# main.net
KiCad netlist of a schematic drawn in Altium Designer
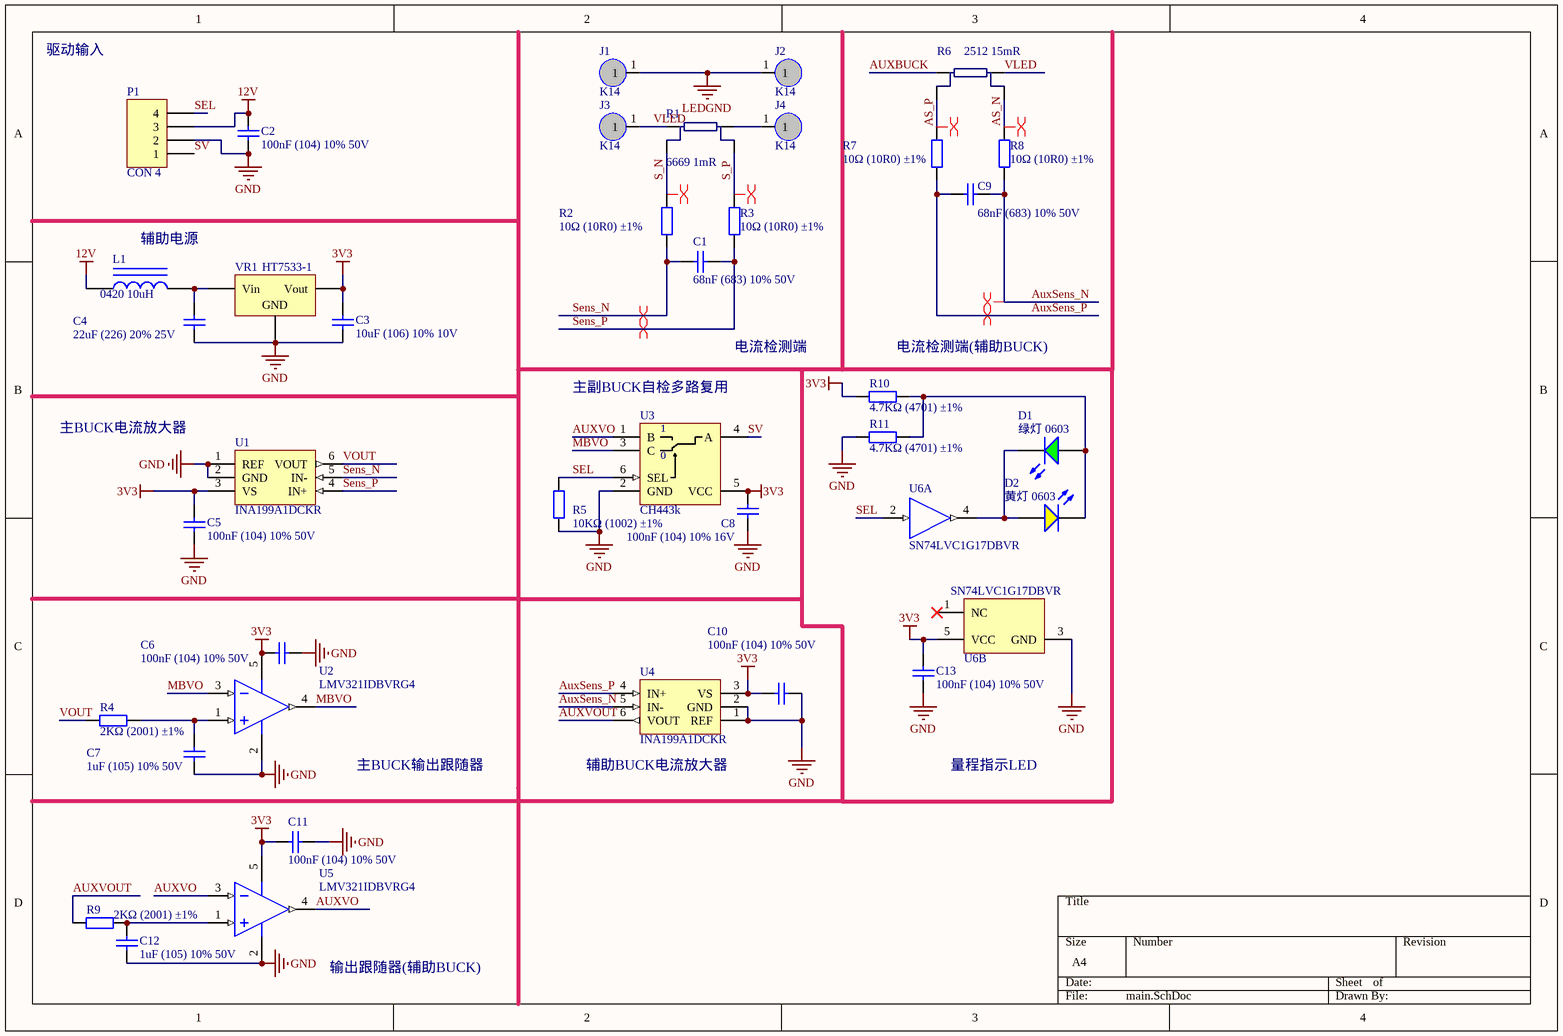
[diagram p0: main.SchDoc]

(export (version "E")
  (design (tool "Eeschema 10.0.6"))
  (components
    (comp (ref "C1")
      (value "68nF (683) 10% 50V")
      (footprint "0603_C")
      (description "贴片电容")
      (libsource (lib "Miscellaneous Devices LC") (part "0603 68nF (683) 10% 50V"))
    )
    (comp (ref "C2")
      (value "100nF (104) 10% 50V")
      (footprint "0603_C")
      (description "贴片电容")
      (libsource (lib "Miscellaneous Devices LC") (part "0603 100nF (104) 10% 50V"))
    )
    (comp (ref "C3")
      (value "10uF (106) 10% 10V")
      (footprint "0603_C")
      (description "贴片电容")
      (libsource (lib "Miscellaneous Devices LC") (part "0603 10uF (106) 10% 10V"))
    )
    (comp (ref "C4")
      (value "22uF (226) 20% 25V")
      (footprint "0805_C")
      (description "贴片电容")
      (libsource (lib "Miscellaneous Devices LC") (part "0805 22uF (226) 20% 25V"))
    )
    (comp (ref "C5")
      (value "100nF (104) 10% 50V")
      (footprint "0603_C")
      (description "贴片电容")
      (libsource (lib "Miscellaneous Devices LC") (part "0603 100nF (104) 10% 50V"))
    )
    (comp (ref "C6")
      (value "100nF (104) 10% 50V")
      (footprint "0603_C")
      (description "贴片电容")
      (libsource (lib "Miscellaneous Devices LC") (part "0603 100nF (104) 10% 50V"))
    )
    (comp (ref "C7")
      (value "1uF (105) 10% 50V")
      (footprint "0603_C")
      (description "贴片电容")
      (libsource (lib "Miscellaneous Devices LC") (part "0603 1uF (105) 10% 50V"))
    )
    (comp (ref "C8")
      (value "100nF (104) 10% 16V")
      (footprint "0402_C")
      (description "贴片电容")
      (libsource (lib "Miscellaneous Devices LC") (part "0402 100nF (104) 10% 16V"))
    )
    (comp (ref "C9")
      (value "68nF (683) 10% 50V")
      (footprint "0603_C")
      (description "贴片电容")
      (libsource (lib "Miscellaneous Devices LC") (part "0603 68nF (683) 10% 50V"))
    )
    (comp (ref "C10")
      (value "100nF (104) 10% 50V")
      (footprint "0603_C")
      (description "贴片电容")
      (libsource (lib "Miscellaneous Devices LC") (part "0603 100nF (104) 10% 50V"))
    )
    (comp (ref "C11")
      (value "100nF (104) 10% 50V")
      (footprint "0603_C")
      (description "贴片电容")
      (libsource (lib "Miscellaneous Devices LC") (part "0603 100nF (104) 10% 50V"))
    )
    (comp (ref "C12")
      (value "1uF (105) 10% 50V")
      (footprint "0603_C")
      (description "贴片电容")
      (libsource (lib "Miscellaneous Devices LC") (part "0603 1uF (105) 10% 50V"))
    )
    (comp (ref "C13")
      (value "100nF (104) 10% 50V")
      (footprint "0603_C")
      (description "贴片电容")
      (libsource (lib "Miscellaneous Devices LC") (part "0603 100nF (104) 10% 50V"))
    )
    (comp (ref "D1")
      (value "绿灯 0603")
      (footprint "0603_LED_S1")
      (description "发光二极管")
      (libsource (lib "Miscellaneous Devices LC") (part "0603 绿灯"))
    )
    (comp (ref "D2")
      (value "黄灯 0603")
      (footprint "0603_LED_S1")
      (description "发光二极管")
      (libsource (lib "Miscellaneous Devices LC") (part "0603 黄灯"))
    )
    (comp (ref "J1") (value "K14") (footprint "k14端子") (libsource (lib "山猫的集成库20190318") (part "Con 1")))
    (comp (ref "J2") (value "K14") (footprint "k14端子") (libsource (lib "山猫的集成库20190318") (part "Con 1")))
    (comp (ref "J3") (value "K14") (footprint "k14端子") (libsource (lib "山猫的集成库20190318") (part "Con 1")))
    (comp (ref "J4") (value "K14") (footprint "k14端子") (libsource (lib "山猫的集成库20190318") (part "Con 1")))
    (comp (ref "L1")
      (value "0420")
      (footprint "IND0420")
      (description "Magnetic-Core Inductor")
      (fields (field (name "ALTIUM_VALUE") "10uH") (field (name "PUBLISHER") "Altium Limited"))
      (libsource (lib "Miscellaneous Devices") (part "Inductor Iron"))
    )
    (comp (ref "P1")
      (value "CON 4")
      (footprint "KF2EDGR5.08/4")
      (description "4-Pin")
      (fields (field (name "PUBLISHER") "Altium Limited"))
      (libsource (lib "山猫的集成库20190318") (part "CON 4"))
    )
    (comp (ref "R1")
      (value "6669 1mR")
      (footprint "Shunt6669")
      (description "4wire shunt 6669 1mR")
      (libsource (lib "custom") (part "shunt"))
    )
    (comp (ref "R2")
      (value "10Ω (10R0) ±1%")
      (footprint "0603_R")
      (description "贴片电阻")
      (libsource (lib "Miscellaneous Devices LC") (part "0603 10Ω (10R0) 1%"))
    )
    (comp (ref "R3")
      (value "10Ω (10R0) ±1%")
      (footprint "0603_R")
      (description "贴片电阻")
      (libsource (lib "Miscellaneous Devices LC") (part "0603 10Ω (10R0) 1%"))
    )
    (comp (ref "R4")
      (value "2KΩ (2001) ±1%")
      (footprint "0603_R")
      (description "贴片电阻")
      (libsource (lib "Miscellaneous Devices LC") (part "0603 2KΩ (2001) 1%"))
    )
    (comp (ref "R5")
      (value "10KΩ (1002) ±1%")
      (footprint "0402_R")
      (description "贴片电阻")
      (libsource (lib "Miscellaneous Devices LC") (part "0402 10KΩ (1002) 1%"))
    )
    (comp (ref "R6")
      (value "2512 15mR")
      (footprint "2512-Virtual4Wire")
      (description "2512检流电阻 15mR")
      (libsource (lib "custom") (part "shunt"))
    )
    (comp (ref "R7")
      (value "10Ω (10R0) ±1%")
      (footprint "0603_R")
      (description "贴片电阻")
      (libsource (lib "Miscellaneous Devices LC") (part "0603 10Ω (10R0) 1%"))
    )
    (comp (ref "R8")
      (value "10Ω (10R0) ±1%")
      (footprint "0603_R")
      (description "贴片电阻")
      (libsource (lib "Miscellaneous Devices LC") (part "0603 10Ω (10R0) 1%"))
    )
    (comp (ref "R9")
      (value "2KΩ (2001) ±1%")
      (footprint "0603_R")
      (description "贴片电阻")
      (libsource (lib "Miscellaneous Devices LC") (part "0603 2KΩ (2001) 1%"))
    )
    (comp (ref "R10")
      (value "4.7KΩ (4701) ±1%")
      (footprint "0603_R")
      (description "贴片电阻")
      (libsource (lib "Miscellaneous Devices LC") (part "0603 4.7KΩ (4701) 1%"))
    )
    (comp (ref "R11")
      (value "4.7KΩ (4701) ±1%")
      (footprint "0603_R")
      (description "贴片电阻")
      (libsource (lib "Miscellaneous Devices LC") (part "0603 4.7KΩ (4701) 1%"))
    )
    (comp (ref "U1")
      (value "INA199A1DCKR")
      (footprint "SC70-6")
      (description "50Khz 50V/V 26V Max High Side Current Op Amp.")
      (libsource (lib "") (part "INA199A2DCKR_1"))
    )
    (comp (ref "U2")
      (value "LMV321IDBVRG4")
      (footprint "SOT-23-5")
      (description "运放")
      (libsource (lib "Miscellaneous Devices LC") (part "LMV321IDBVRG4_[C7972]"))
    )
    (comp (ref "U3")
      (value "CH443k")
      (footprint "SC70-6")
      (description "Low-Voltage Analog Switch SPDT,1.8-5V Power")
      (libsource (lib "custom") (part "NC7SB3157P6X"))
    )
    (comp (ref "U4")
      (value "INA199A1DCKR")
      (footprint "SC70-6")
      (description "50Khz 50V/V 26V Max High Side Current Op Amp.")
      (libsource (lib "custom") (part "INA199A2DCKR"))
    )
    (comp (ref "U5")
      (value "LMV321IDBVRG4")
      (footprint "SOT-23-5")
      (description "运放")
      (libsource (lib "Miscellaneous Devices LC") (part "LMV321IDBVRG4_[C7972]"))
    )
    (comp (ref "U6")
      (value "SN74LVC1G17DBVR")
      (footprint "DBV0005A_N")
      (description "Single Schmitt-Trigger Buffer, DBV0005A, LARGE T&R")
      (fields
        (field (name "GENERIC PART NUMBER") "SN74LVC1G17")
        (field (name "MANUFACTURER") "Texas Instruments")
      )
      (libsource (lib "TI_Logic_Little_Logic") (part "SN74LVC1G17DBVR"))
    )
    (comp (ref "VR1")
      (value "HT7533-1")
      (footprint "SOT-89(SOT-89-3)")
      (description "低压差线性稳压(LDO)")
      (libsource (lib "Miscellaneous Devices LC") (part "SOT-89 HT7533-1"))
    )
  )
  (nets
    (net (code "1") (name "/AS_N") (class "Default")
      (node (ref "R6") (pin "3") (pinfunction "CIN_3") (pintype "passive"))
      (node (ref "R8") (pin "2") (pinfunction "2_2") (pintype "passive"))
    )
    (net (code "2") (name "/AS_P") (class "Default")
      (node (ref "R6") (pin "2") (pinfunction "CIN_2") (pintype "passive"))
      (node (ref "R7") (pin "2") (pinfunction "2_2") (pintype "passive"))
    )
    (net (code "3") (name "/AUXBUCK") (class "Default")
      (node (ref "R6") (pin "0") (pinfunction "CIN_0") (pintype "passive"))
    )
    (net (code "4") (name "/AUXVO") (class "Default")
      (node (ref "U3") (pin "1") (pinfunction "B_1") (pintype "passive"))
      (node (ref "U5") (pin "3") (pinfunction "IN-_3") (pintype "input"))
      (node (ref "U5") (pin "4") (pinfunction "OUT_4") (pintype "output"))
    )
    (net (code "5") (name "/AUXVOUT") (class "Default")
      (node (ref "R9") (pin "1") (pinfunction "1_1") (pintype "passive"))
      (node (ref "U4") (pin "6") (pinfunction "VOUT_6") (pintype "output"))
    )
    (net (code "6") (name "/AuxSens_N") (class "Default")
      (node (ref "C9") (pin "2") (pinfunction "2_2") (pintype "passive"))
      (node (ref "R8") (pin "1") (pinfunction "1_1") (pintype "passive"))
      (node (ref "U4") (pin "5") (pinfunction "IN-_5") (pintype "input"))
    )
    (net (code "7") (name "/AuxSens_P") (class "Default")
      (node (ref "C9") (pin "1") (pinfunction "1_1") (pintype "passive"))
      (node (ref "R7") (pin "1") (pinfunction "1_1") (pintype "passive"))
      (node (ref "U4") (pin "4") (pinfunction "IN+_4") (pintype "input"))
    )
    (net (code "8") (name "/MBVO") (class "Default")
      (node (ref "U2") (pin "3") (pinfunction "IN-_3") (pintype "input"))
      (node (ref "U2") (pin "4") (pinfunction "OUT_4") (pintype "output"))
      (node (ref "U3") (pin "3") (pinfunction "C_3") (pintype "passive"))
    )
    (net (code "9") (name "/SEL") (class "Default")
      (node (ref "P1") (pin "4") (pinfunction "4_4") (pintype "passive"))
      (node (ref "R5") (pin "2") (pinfunction "2_2") (pintype "passive"))
      (node (ref "U3") (pin "6") (pinfunction "SEL_6") (pintype "input"))
      (node (ref "U6") (pin "2") (pinfunction "A_2") (pintype "input"))
    )
    (net (code "10") (name "/SV") (class "Default")
      (node (ref "P1") (pin "1") (pinfunction "1_1") (pintype "passive"))
      (node (ref "U3") (pin "4") (pinfunction "A_4") (pintype "passive"))
    )
    (net (code "11") (name "/S_N") (class "Default")
      (node (ref "R1") (pin "2") (pinfunction "CIN_2") (pintype "passive"))
      (node (ref "R2") (pin "2") (pinfunction "2_2") (pintype "passive"))
    )
    (net (code "12") (name "/S_P") (class "Default")
      (node (ref "R1") (pin "3") (pinfunction "CIN_3") (pintype "passive"))
      (node (ref "R3") (pin "2") (pinfunction "2_2") (pintype "passive"))
    )
    (net (code "13") (name "/Sens_N") (class "Default")
      (node (ref "C1") (pin "1") (pinfunction "1_1") (pintype "passive"))
      (node (ref "R2") (pin "1") (pinfunction "1_1") (pintype "passive"))
      (node (ref "U1") (pin "5") (pinfunction "IN-_5") (pintype "input"))
    )
    (net (code "14") (name "/Sens_P") (class "Default")
      (node (ref "C1") (pin "2") (pinfunction "2_2") (pintype "passive"))
      (node (ref "R3") (pin "1") (pinfunction "1_1") (pintype "passive"))
      (node (ref "U1") (pin "4") (pinfunction "IN+_4") (pintype "input"))
    )
    (net (code "15") (name "/VLED") (class "Default")
      (node (ref "J3") (pin "1") (pinfunction "1_1") (pintype "passive"))
      (node (ref "R1") (pin "0") (pinfunction "CIN_0") (pintype "passive"))
      (node (ref "R6") (pin "1") (pinfunction "CIN_1") (pintype "passive"))
    )
    (net (code "16") (name "/VOUT") (class "Default")
      (node (ref "R4") (pin "1") (pinfunction "1_1") (pintype "passive"))
      (node (ref "U1") (pin "6") (pinfunction "VOUT_6") (pintype "output"))
    )
    (net (code "17") (name "3V3") (class "Default")
      (node (ref "C10") (pin "2") (pinfunction "2_2") (pintype "passive"))
      (node (ref "C11") (pin "1") (pinfunction "1_1") (pintype "passive"))
      (node (ref "C13") (pin "2") (pinfunction "2_2") (pintype "passive"))
      (node (ref "C3") (pin "2") (pinfunction "2_2") (pintype "passive"))
      (node (ref "C5") (pin "2") (pinfunction "2_2") (pintype "passive"))
      (node (ref "C6") (pin "1") (pinfunction "1_1") (pintype "passive"))
      (node (ref "C8") (pin "2") (pinfunction "2_2") (pintype "passive"))
      (node (ref "R10") (pin "2") (pinfunction "2_2") (pintype "passive"))
      (node (ref "U1") (pin "3") (pinfunction "VS_3") (pintype "passive"))
      (node (ref "U2") (pin "5") (pinfunction "V+_5") (pintype "power_in"))
      (node (ref "U3") (pin "5") (pinfunction "VCC_5") (pintype "power_in"))
      (node (ref "U4") (pin "3") (pinfunction "VS_3") (pintype "passive"))
      (node (ref "U5") (pin "5") (pinfunction "V+_5") (pintype "power_in"))
      (node (ref "U6") (pin "5") (pinfunction "VCC_5") (pintype "power_in"))
      (node (ref "VR1") (pin "3") (pinfunction "Vout_3") (pintype "passive"))
    )
    (net (code "18") (name "12V") (class "Default")
      (node (ref "C2") (pin "2") (pinfunction "2_2") (pintype "passive"))
      (node (ref "L1") (pin "1") (pinfunction "1_1") (pintype "passive"))
      (node (ref "P1") (pin "3") (pinfunction "3_3") (pintype "passive"))
    )
    (net (code "19") (name "GND") (class "Default")
      (node (ref "C10") (pin "1") (pinfunction "1_1") (pintype "passive"))
      (node (ref "C11") (pin "2") (pinfunction "2_2") (pintype "passive"))
      (node (ref "C12") (pin "1") (pinfunction "1_1") (pintype "passive"))
      (node (ref "C13") (pin "1") (pinfunction "1_1") (pintype "passive"))
      (node (ref "C2") (pin "1") (pinfunction "1_1") (pintype "passive"))
      (node (ref "C3") (pin "1") (pinfunction "1_1") (pintype "passive"))
      (node (ref "C4") (pin "1") (pinfunction "1_1") (pintype "passive"))
      (node (ref "C5") (pin "1") (pinfunction "1_1") (pintype "passive"))
      (node (ref "C6") (pin "2") (pinfunction "2_2") (pintype "passive"))
      (node (ref "C7") (pin "1") (pinfunction "1_1") (pintype "passive"))
      (node (ref "C8") (pin "1") (pinfunction "1_1") (pintype "passive"))
      (node (ref "P1") (pin "2") (pinfunction "2_2") (pintype "passive"))
      (node (ref "R11") (pin "2") (pinfunction "2_2") (pintype "passive"))
      (node (ref "R5") (pin "1") (pinfunction "1_1") (pintype "passive"))
      (node (ref "U1") (pin "1") (pinfunction "REF_1") (pintype "passive"))
      (node (ref "U1") (pin "2") (pinfunction "GND_2") (pintype "passive"))
      (node (ref "U2") (pin "2") (pinfunction "V-_2") (pintype "power_in"))
      (node (ref "U3") (pin "2") (pinfunction "GND_2") (pintype "power_in"))
      (node (ref "U4") (pin "1") (pinfunction "REF_1") (pintype "passive"))
      (node (ref "U4") (pin "2") (pinfunction "GND_2") (pintype "passive"))
      (node (ref "U5") (pin "2") (pinfunction "V-_2") (pintype "power_in"))
      (node (ref "U6") (pin "3") (pinfunction "GND_3") (pintype "power_in"))
      (node (ref "VR1") (pin "1") (pinfunction "GND_1") (pintype "passive"))
    )
    (net (code "20") (name "LEDGND") (class "Default")
      (node (ref "J1") (pin "1") (pinfunction "1_1") (pintype "passive"))
      (node (ref "J2") (pin "1") (pinfunction "1_1") (pintype "passive"))
    )
    (net (code "21") (name "Net-(D1-PadA)") (class "Default")
      (node (ref "D1") (pin "A") (pinfunction "A_A") (pintype "passive"))
      (node (ref "D2") (pin "K") (pinfunction "K_K") (pintype "passive"))
      (node (ref "R10") (pin "1") (pinfunction "1_1") (pintype "passive"))
      (node (ref "R11") (pin "1") (pinfunction "1_1") (pintype "passive"))
    )
    (net (code "22") (name "Net-(J4-Pad1)") (class "Default")
      (node (ref "J4") (pin "1") (pinfunction "1_1") (pintype "passive"))
      (node (ref "R1") (pin "1") (pinfunction "CIN_1") (pintype "passive"))
    )
    (net (code "23") (name "Net-(U2-IN+)") (class "Default")
      (node (ref "C7") (pin "2") (pinfunction "2_2") (pintype "passive"))
      (node (ref "R4") (pin "2") (pinfunction "2_2") (pintype "passive"))
      (node (ref "U2") (pin "1") (pinfunction "IN+_1") (pintype "input"))
    )
    (net (code "24") (name "Net-(U5-IN+)") (class "Default")
      (node (ref "C12") (pin "2") (pinfunction "2_2") (pintype "passive"))
      (node (ref "R9") (pin "2") (pinfunction "2_2") (pintype "passive"))
      (node (ref "U5") (pin "1") (pinfunction "IN+_1") (pintype "input"))
    )
    (net (code "25") (name "Net-(U6A-Y)") (class "Default")
      (node (ref "D1") (pin "K") (pinfunction "K_K") (pintype "passive"))
      (node (ref "D2") (pin "A") (pinfunction "A_A") (pintype "passive"))
      (node (ref "U6") (pin "4") (pinfunction "Y_4") (pintype "output"))
    )
    (net (code "26") (name "Net-(VR1-Vin)") (class "Default")
      (node (ref "C4") (pin "2") (pinfunction "2_2") (pintype "passive"))
      (node (ref "L1") (pin "2") (pinfunction "2_2") (pintype "passive"))
      (node (ref "VR1") (pin "2") (pinfunction "Vin_2") (pintype "passive"))
    )
    (net (code "27") (name "unconnected-(U6B-NC-Pad1)") (class "Default")
      (node (ref "U6") (pin "1") (pinfunction "NC_1") (pintype "passive+no_connect"))
    )
  )
)
